# CC_pwr-moteur.net
KiCad netlist of a schematic drawn in Altium Designer
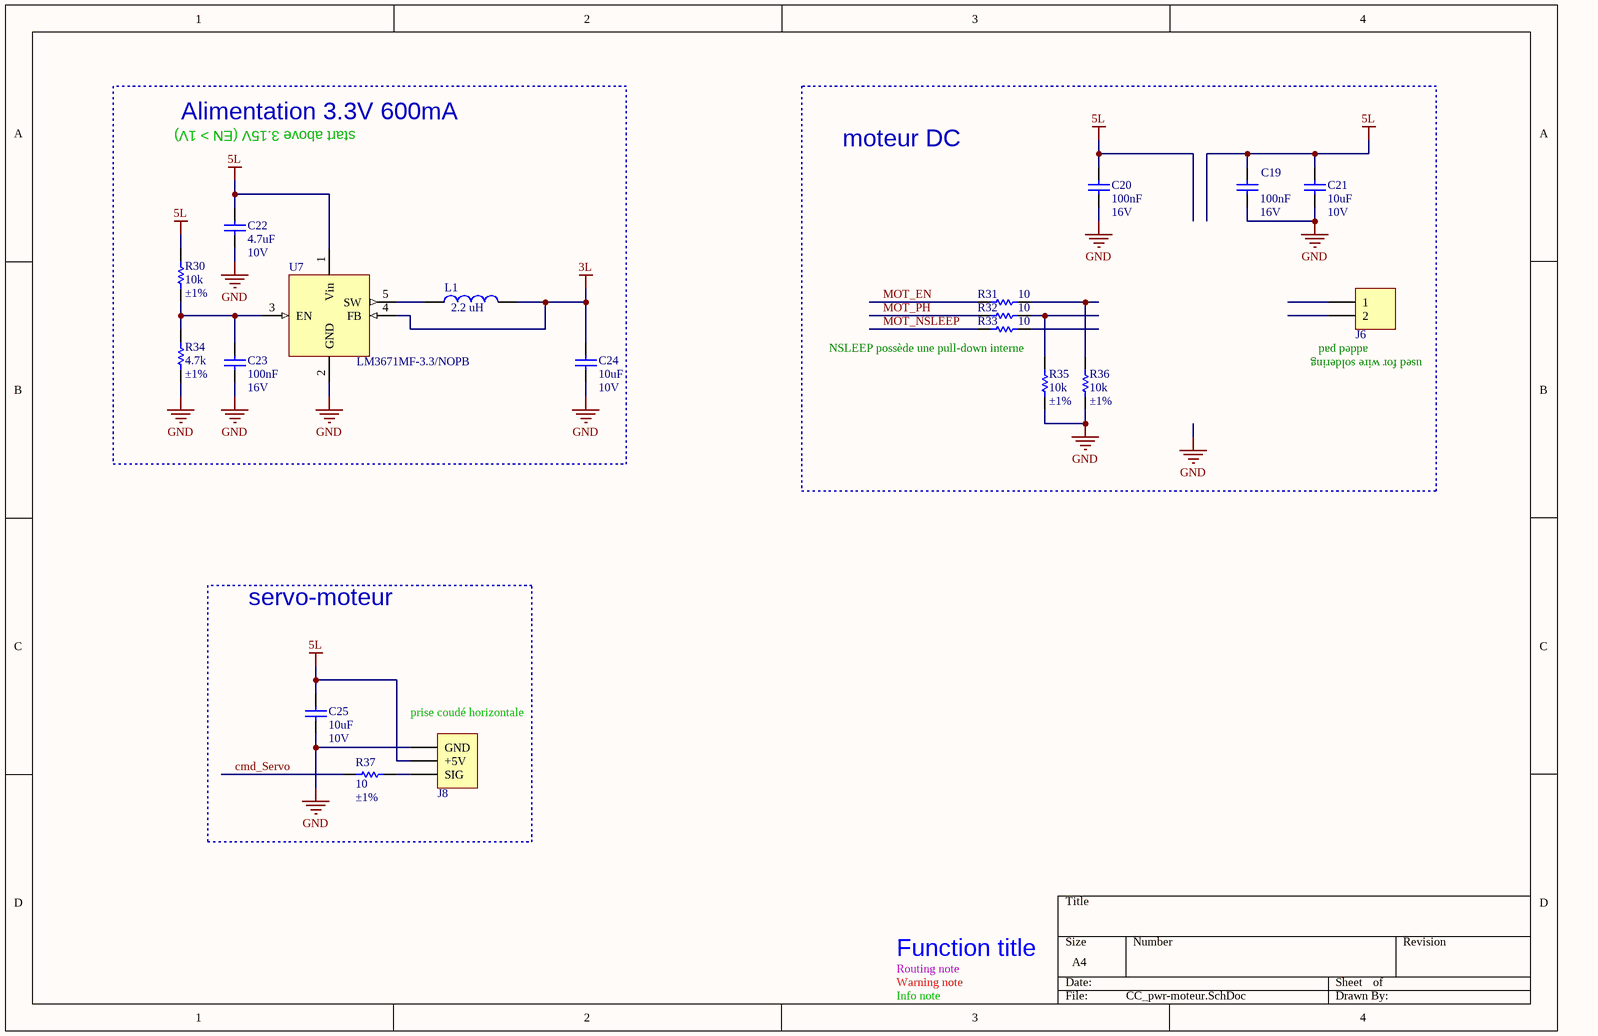
[diagram p0: CC_pwr-moteur.SchDoc]

(export (version "E")
  (design (tool "Eeschema 10.0.6"))
  (components
    (comp (ref "C19")
      (value "100nF")
      (footprint "WCAP-CSGP_0402, 1x0.5x0.5")
      (description "CAP CER 100nF 16V X7R 0402")
      (fields
        (field (name "MANUFACTURER") "Wurth Elektronik")
        (field (name "MANUFACTURER PART NUMBER") "885012205037")
        (field (name "RATEDVOLTAGE") "16V")
      )
      (libsource (lib "Condensateur") (part "WCAP-CSGP, 885012205037"))
    )
    (comp (ref "C20")
      (value "100nF")
      (footprint "WCAP-CSGP_0402, 1x0.5x0.5")
      (description "CAP CER 100nF 16V X7R 0402")
      (fields
        (field (name "MANUFACTURER") "Wurth Elektronik")
        (field (name "MANUFACTURER PART NUMBER") "885012205037")
        (field (name "RATEDVOLTAGE") "16V")
      )
      (libsource (lib "Condensateur") (part "WCAP-CSGP, 885012205037"))
    )
    (comp (ref "C21")
      (value "10uF")
      (footprint "WCAP-CSGP_0805, 2x1.25x1.25")
      (description "CAP CER 10uF 10V X7R 0805")
      (fields
        (field (name "MANUFACTURER") "Wurth Elektronik")
        (field (name "MANUFACTURER PART NUMBER") "885012207026")
        (field (name "RATEDVOLTAGE") "10V")
      )
      (libsource (lib "Condensateur") (part "WCAP-CSGP, 885012207026"))
    )
    (comp (ref "C22")
      (value "4.7uF")
      (footprint "WCAP-CSGP_0603, 1.6x0.8x0.8")
      (description "CAP CER 4.7UF 10V X5R 0603")
      (fields
        (field (name "MANUFACTURER") "Wurth Elektronik")
        (field (name "MANUFACTURER PART NUMBER") "885012106012")
        (field (name "RATEDVOLTAGE") "10V")
      )
      (libsource (lib "Condensateur") (part "WCAP-CSGP, 885012106012"))
    )
    (comp (ref "C23")
      (value "100nF")
      (footprint "WCAP-CSGP_0402, 1x0.5x0.5")
      (description "CAP CER 100nF 16V X7R 0402")
      (fields
        (field (name "MANUFACTURER") "Wurth Elektronik")
        (field (name "MANUFACTURER PART NUMBER") "885012205037")
        (field (name "RATEDVOLTAGE") "16V")
      )
      (libsource (lib "Condensateur") (part "WCAP-CSGP, 885012205037"))
    )
    (comp (ref "C24")
      (value "10uF")
      (footprint "WCAP-CSGP_0805, 2x1.25x1.25")
      (description "CAP CER 10uF 10V X7R 0805")
      (fields
        (field (name "MANUFACTURER") "Wurth Elektronik")
        (field (name "MANUFACTURER PART NUMBER") "885012207026")
        (field (name "RATEDVOLTAGE") "10V")
      )
      (libsource (lib "Condensateur") (part "WCAP-CSGP, 885012207026"))
    )
    (comp (ref "C25")
      (value "10uF")
      (footprint "WCAP-CSGP_0805, 2x1.25x1.25")
      (description "CAP CER 10uF 10V X7R 0805")
      (fields
        (field (name "MANUFACTURER") "Wurth Elektronik")
        (field (name "MANUFACTURER PART NUMBER") "885012207026")
        (field (name "RATEDVOLTAGE") "10V")
      )
      (libsource (lib "Condensateur") (part "WCAP-CSGP, 885012207026"))
    )
    (comp (ref "J6")
      (value "653102131822")
      (footprint "653102131822")
      (description "WR-WTB 1.25mm")
      (libsource (lib "Connecteurs") (part "653102131822"))
    )
    (comp (ref "J8")
      (value "61300311021")
      (footprint "61300311021")
      (description "CONN HEADER 3 POS RA 2.54mm")
      (fields (field (name "MANUFACTURER") "Wurth Electronics Inc."))
      (libsource (lib "Connecteurs") (part "61300311021"))
    )
    (comp (ref "L1")
      (value "2.2 uH")
      (footprint "WE-LQS_2010")
      (description "FIXED IND 2.2UH 960MA 220 MOHM")
      (fields
        (field (name "MANUFACTURER") "Wurth Elektronik")
        (field (name "MANUFACTURER PART NUMBER") "74404020022")
      )
      (libsource (lib "Inductance") (part "74404020022"))
    )
    (comp (ref "R30")
      (value "10k")
      (footprint "RESC1005X04N")
      (description "RES SMD 10K OHM 1% 1/16W 0402")
      (fields
        (field (name "POWER") "63mW")
        (field (name "MANUFACTURER") "Yageo")
        (field (name "PRECISION") "±1%")
      )
      (libsource (lib "Resistance") (part "RC0402FR-0710KL"))
    )
    (comp (ref "R31")
      (value "10")
      (footprint "RESC1005X04N")
      (description "RES SMD 10 OHM 1% 1/16W 0402")
      (fields (field (name "POWER") "63mW") (field (name "MANUFACTURER") "Yageo"))
      (libsource (lib "Resistance") (part "RC0402FR-0710RL"))
    )
    (comp (ref "R32")
      (value "10")
      (footprint "RESC1005X04N")
      (description "RES SMD 10 OHM 1% 1/16W 0402")
      (fields (field (name "POWER") "63mW") (field (name "MANUFACTURER") "Yageo"))
      (libsource (lib "Resistance") (part "RC0402FR-0710RL"))
    )
    (comp (ref "R33")
      (value "10")
      (footprint "RESC1005X04N")
      (description "RES SMD 10 OHM 1% 1/16W 0402")
      (fields (field (name "POWER") "63mW") (field (name "MANUFACTURER") "Yageo"))
      (libsource (lib "Resistance") (part "RC0402FR-0710RL"))
    )
    (comp (ref "R34")
      (value "4.7k")
      (footprint "RESC1005X04N")
      (description "RES SMD 4K7 OHM 1% 1/16W 0402")
      (fields
        (field (name "POWER") "63mW")
        (field (name "MANUFACTURER") "Yageo")
        (field (name "PRECISION") "±1%")
      )
      (libsource (lib "Resistance") (part "RC0402FR-074K7L"))
    )
    (comp (ref "R35")
      (value "10k")
      (footprint "RESC1005X04N")
      (description "RES SMD 10K OHM 1% 1/16W 0402")
      (fields
        (field (name "POWER") "63mW")
        (field (name "MANUFACTURER") "Yageo")
        (field (name "PRECISION") "±1%")
      )
      (libsource (lib "Resistance") (part "RC0402FR-0710KL"))
    )
    (comp (ref "R36")
      (value "10k")
      (footprint "RESC1005X04N")
      (description "RES SMD 10K OHM 1% 1/16W 0402")
      (fields
        (field (name "POWER") "63mW")
        (field (name "MANUFACTURER") "Yageo")
        (field (name "PRECISION") "±1%")
      )
      (libsource (lib "Resistance") (part "RC0402FR-0710KL"))
    )
    (comp (ref "R37")
      (value "10")
      (footprint "RESC1005X04N")
      (description "RES SMD 10 OHM 1% 1/16W 0402")
      (fields
        (field (name "POWER") "63mW")
        (field (name "MANUFACTURER") "Yageo")
        (field (name "PRECISION") "±1%")
      )
      (libsource (lib "Resistance") (part "RC0402FR-0710RL"))
    )
    (comp (ref "U7")
      (value "LM3671MF-3.3/NOPB")
      (footprint "SOT23-5")
      (description "IC REG BUCK 3.3V 0.6A SYNC SOT23")
      (fields (field (name "MANUFACTURER") "Texas Instruments"))
      (libsource (lib "Alimentation") (part "LM3671MF-3.3/NOPB"))
    )
  )
  (nets
    (net (code "1") (name "/MOT_EN") (class "Default")
      (node (ref "R31") (pin "1") (pinfunction "1_1") (pintype "passive"))
    )
    (net (code "2") (name "/MOT_NSLEEP") (class "Default")
      (node (ref "R33") (pin "1") (pinfunction "1_1") (pintype "passive"))
    )
    (net (code "3") (name "/MOT_PH") (class "Default")
      (node (ref "R32") (pin "1") (pinfunction "1_1") (pintype "passive"))
    )
    (net (code "4") (name "/cmd_Servo") (class "Default")
      (node (ref "R37") (pin "1") (pinfunction "1_1") (pintype "passive"))
    )
    (net (code "5") (name "3L") (class "Default")
      (node (ref "C24") (pin "2") (pinfunction "2_2") (pintype "passive"))
      (node (ref "L1") (pin "2") (pinfunction "2_2") (pintype "passive"))
      (node (ref "U7") (pin "4") (pinfunction "FB_4") (pintype "input"))
    )
    (net (code "6") (name "5L") (class "Default")
      (node (ref "C19") (pin "2") (pinfunction "2_2") (pintype "passive"))
      (node (ref "C20") (pin "2") (pinfunction "2_2") (pintype "passive"))
      (node (ref "C21") (pin "2") (pinfunction "2_2") (pintype "passive"))
      (node (ref "C22") (pin "2") (pinfunction "2_2") (pintype "passive"))
      (node (ref "C25") (pin "2") (pinfunction "2_2") (pintype "passive"))
      (node (ref "J8") (pin "2") (pinfunction "+5V_2") (pintype "passive"))
      (node (ref "R30") (pin "2") (pinfunction "2_2") (pintype "passive"))
      (node (ref "U7") (pin "1") (pinfunction "Vin_1") (pintype "power_in"))
    )
    (net (code "7") (name "GND") (class "Default")
      (node (ref "C19") (pin "1") (pinfunction "1_1") (pintype "passive"))
      (node (ref "C20") (pin "1") (pinfunction "1_1") (pintype "passive"))
      (node (ref "C21") (pin "1") (pinfunction "1_1") (pintype "passive"))
      (node (ref "C22") (pin "1") (pinfunction "1_1") (pintype "passive"))
      (node (ref "C23") (pin "1") (pinfunction "1_1") (pintype "passive"))
      (node (ref "C24") (pin "1") (pinfunction "1_1") (pintype "passive"))
      (node (ref "C25") (pin "1") (pinfunction "1_1") (pintype "passive"))
      (node (ref "J8") (pin "1") (pinfunction "GND_1") (pintype "passive"))
      (node (ref "R34") (pin "1") (pinfunction "1_1") (pintype "passive"))
      (node (ref "R35") (pin "1") (pinfunction "1_1") (pintype "passive"))
      (node (ref "R36") (pin "1") (pinfunction "1_1") (pintype "passive"))
      (node (ref "U7") (pin "2") (pinfunction "GND_2") (pintype "power_in"))
    )
    (net (code "8") (name "Net-(J8-SIG)") (class "Default")
      (node (ref "J8") (pin "3") (pinfunction "SIG_3") (pintype "passive"))
      (node (ref "R37") (pin "2") (pinfunction "2_2") (pintype "passive"))
    )
    (net (code "9") (name "Net-(R31-Pad2)") (class "Default")
      (node (ref "R31") (pin "2") (pinfunction "2_2") (pintype "passive"))
      (node (ref "R36") (pin "2") (pinfunction "2_2") (pintype "passive"))
    )
    (net (code "10") (name "Net-(R32-Pad2)") (class "Default")
      (node (ref "R32") (pin "2") (pinfunction "2_2") (pintype "passive"))
      (node (ref "R35") (pin "2") (pinfunction "2_2") (pintype "passive"))
    )
    (net (code "11") (name "Net-(U7-EN)") (class "Default")
      (node (ref "C23") (pin "2") (pinfunction "2_2") (pintype "passive"))
      (node (ref "R30") (pin "1") (pinfunction "1_1") (pintype "passive"))
      (node (ref "R34") (pin "2") (pinfunction "2_2") (pintype "passive"))
      (node (ref "U7") (pin "3") (pinfunction "EN_3") (pintype "input"))
    )
    (net (code "12") (name "Net-(U7-SW)") (class "Default")
      (node (ref "L1") (pin "1") (pinfunction "1_1") (pintype "passive"))
      (node (ref "U7") (pin "5") (pinfunction "SW_5") (pintype "output"))
    )
    (net (code "13") (name "unconnected-(J6-Pad1)") (class "Default")
      (node (ref "J6") (pin "1") (pinfunction "1_1") (pintype "passive"))
    )
    (net (code "14") (name "unconnected-(J6-Pad2)") (class "Default")
      (node (ref "J6") (pin "2") (pinfunction "2_2") (pintype "passive"))
    )
    (net (code "15") (name "unconnected-(R33-Pad2)") (class "Default")
      (node (ref "R33") (pin "2") (pinfunction "2_2") (pintype "passive"))
    )
  )
)
